# WiFly.net
KiCad netlist of a schematic drawn in EAGLE
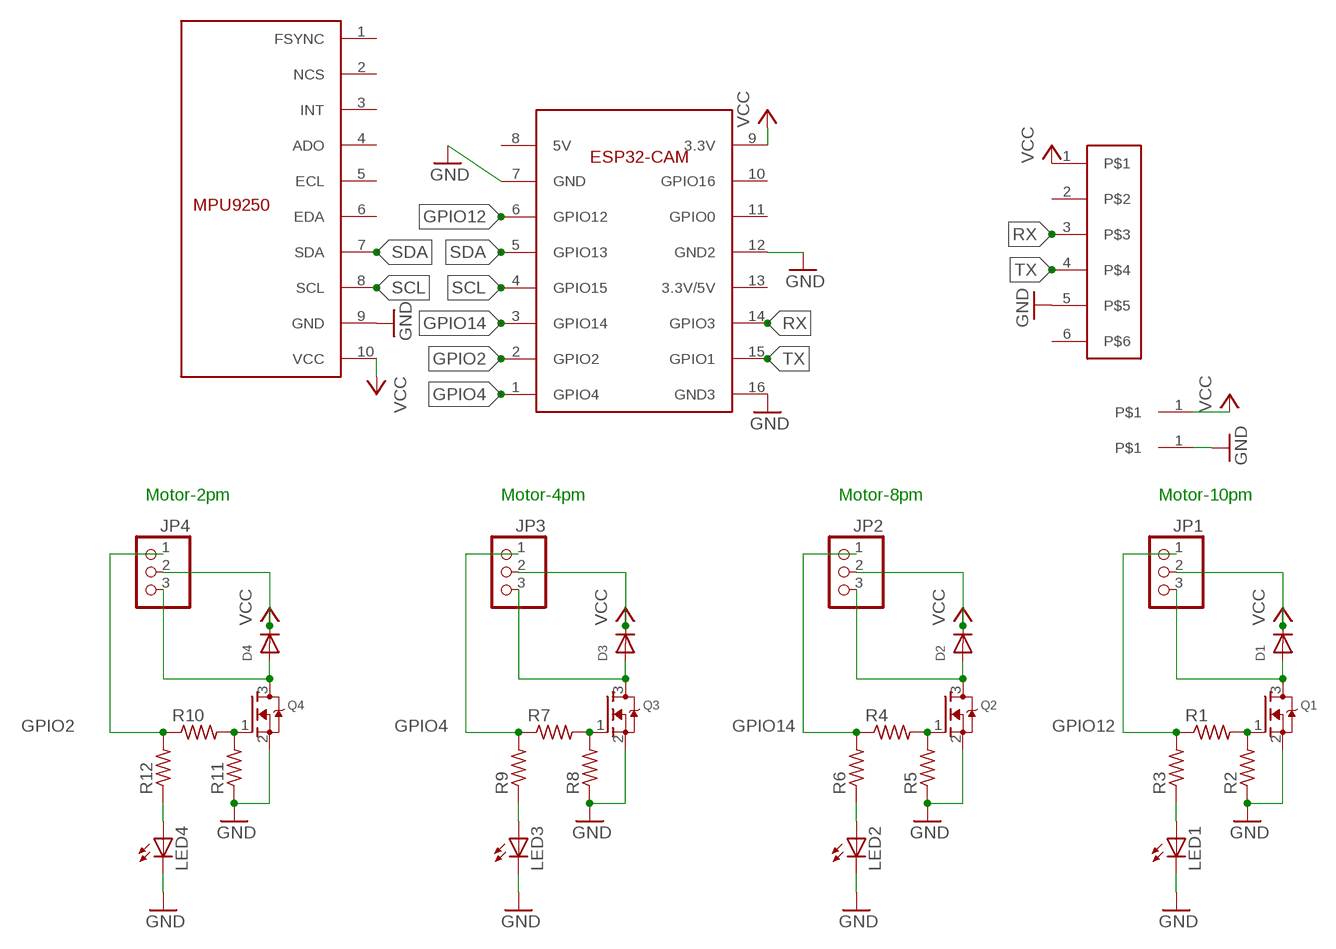
[diagram p0: schematic, sheet 1]

(export (version "E")
  (design (tool "Eeschema 10.0.6"))
  (components
    (comp (ref "+")
      (value "22AWG22AWG-MALE")
      (footprint "eagle-import:HDRV1W64P0_1X1_193X193X447B")
      (libsource (lib "eagle-import") (part "22AWG22AWG-MALE"))
    )
    (comp (ref "-")
      (value "22AWG22AWG-MALE")
      (footprint "eagle-import:HDRV1W64P0_1X1_193X193X447B")
      (libsource (lib "eagle-import") (part "22AWG22AWG-MALE"))
    )
    (comp (ref "D1")
      (value "DIODESOD-323F")
      (footprint "eagle-import:SOD-323F")
      (libsource (lib "eagle-import") (part "DIODESOD-323F"))
    )
    (comp (ref "D2")
      (value "DIODESOD-323F")
      (footprint "eagle-import:SOD-323F")
      (libsource (lib "eagle-import") (part "DIODESOD-323F"))
    )
    (comp (ref "D3")
      (value "DIODESOD-323F")
      (footprint "eagle-import:SOD-323F")
      (libsource (lib "eagle-import") (part "DIODESOD-323F"))
    )
    (comp (ref "D4")
      (value "DIODESOD-323F")
      (footprint "eagle-import:SOD-323F")
      (libsource (lib "eagle-import") (part "DIODESOD-323F"))
    )
    (comp (ref "JP1")
      (value "PINHD-1X3CB")
      (footprint "eagle-import:1X03-CLEANBIG")
      (libsource (lib "eagle-import") (part "PINHD-1X3CB"))
    )
    (comp (ref "JP2")
      (value "PINHD-1X3CB")
      (footprint "eagle-import:1X03-CLEANBIG")
      (libsource (lib "eagle-import") (part "PINHD-1X3CB"))
    )
    (comp (ref "JP3")
      (value "PINHD-1X3CB")
      (footprint "eagle-import:1X03-CLEANBIG")
      (libsource (lib "eagle-import") (part "PINHD-1X3CB"))
    )
    (comp (ref "JP4")
      (value "PINHD-1X3CB")
      (footprint "eagle-import:1X03-CLEANBIG")
      (libsource (lib "eagle-import") (part "PINHD-1X3CB"))
    )
    (comp (ref "LED1")
      (value "LEDCHIP-LED0603")
      (footprint "eagle-import:CHIP-LED0603")
      (libsource (lib "eagle-import") (part "LEDCHIP-LED0603"))
    )
    (comp (ref "LED2")
      (value "LEDCHIP-LED0603")
      (footprint "eagle-import:CHIP-LED0603")
      (libsource (lib "eagle-import") (part "LEDCHIP-LED0603"))
    )
    (comp (ref "LED3")
      (value "LEDCHIP-LED0603")
      (footprint "eagle-import:CHIP-LED0603")
      (libsource (lib "eagle-import") (part "LEDCHIP-LED0603"))
    )
    (comp (ref "LED4")
      (value "LEDCHIP-LED0603")
      (footprint "eagle-import:CHIP-LED0603")
      (libsource (lib "eagle-import") (part "LEDCHIP-LED0603"))
    )
    (comp (ref "Q1")
      (value "MOSFET-NREFLOW")
      (footprint "eagle-import:SOT23")
      (libsource (lib "eagle-import") (part "MOSFET-NREFLOW"))
    )
    (comp (ref "Q2")
      (value "MOSFET-NREFLOW")
      (footprint "eagle-import:SOT23")
      (libsource (lib "eagle-import") (part "MOSFET-NREFLOW"))
    )
    (comp (ref "Q3")
      (value "MOSFET-NREFLOW")
      (footprint "eagle-import:SOT23")
      (libsource (lib "eagle-import") (part "MOSFET-NREFLOW"))
    )
    (comp (ref "Q4")
      (value "MOSFET-NREFLOW")
      (footprint "eagle-import:SOT23")
      (libsource (lib "eagle-import") (part "MOSFET-NREFLOW"))
    )
    (comp (ref "R1")
      (value "R-US_R0603")
      (footprint "eagle-import:R0603")
      (libsource (lib "eagle-import") (part "R-US_R0603"))
    )
    (comp (ref "R2")
      (value "R-US_R0603")
      (footprint "eagle-import:R0603")
      (libsource (lib "eagle-import") (part "R-US_R0603"))
    )
    (comp (ref "R3")
      (value "R-US_R0603")
      (footprint "eagle-import:R0603")
      (libsource (lib "eagle-import") (part "R-US_R0603"))
    )
    (comp (ref "R4")
      (value "R-US_R0603")
      (footprint "eagle-import:R0603")
      (libsource (lib "eagle-import") (part "R-US_R0603"))
    )
    (comp (ref "R5")
      (value "R-US_R0603")
      (footprint "eagle-import:R0603")
      (libsource (lib "eagle-import") (part "R-US_R0603"))
    )
    (comp (ref "R6")
      (value "R-US_R0603")
      (footprint "eagle-import:R0603")
      (libsource (lib "eagle-import") (part "R-US_R0603"))
    )
    (comp (ref "R7")
      (value "R-US_R0603")
      (footprint "eagle-import:R0603")
      (libsource (lib "eagle-import") (part "R-US_R0603"))
    )
    (comp (ref "R8")
      (value "R-US_R0603")
      (footprint "eagle-import:R0603")
      (libsource (lib "eagle-import") (part "R-US_R0603"))
    )
    (comp (ref "R9")
      (value "R-US_R0603")
      (footprint "eagle-import:R0603")
      (libsource (lib "eagle-import") (part "R-US_R0603"))
    )
    (comp (ref "R10")
      (value "R-US_R0603")
      (footprint "eagle-import:R0603")
      (libsource (lib "eagle-import") (part "R-US_R0603"))
    )
    (comp (ref "R11")
      (value "R-US_R0603")
      (footprint "eagle-import:R0603")
      (libsource (lib "eagle-import") (part "R-US_R0603"))
    )
    (comp (ref "R12")
      (value "R-US_R0603")
      (footprint "eagle-import:R0603")
      (libsource (lib "eagle-import") (part "R-US_R0603"))
    )
    (comp (ref "U$1")
      (value "MPU9250FEMALE_HEADER")
      (footprint "eagle-import:HDRVR10W64P254_1X10_2540X254X254B")
      (libsource (lib "eagle-import") (part "MPU9250FEMALE_HEADER"))
    )
    (comp (ref "U$2")
      (value "ESP32-CAMESP32-CAM")
      (footprint "eagle-import:HDRVR16W64P2286X254_2X8_2032X2540X254B")
      (libsource (lib "eagle-import") (part "ESP32-CAMESP32-CAM"))
    )
    (comp (ref "U$3")
      (value "6-PINFEMALE-6-PIN-A")
      (footprint "eagle-import:HDRVR6W64P254_1X6_1524X254X762B")
      (libsource (lib "eagle-import") (part "6-PINFEMALE-6-PIN-A"))
    )
  )
  (nets
    (net (code "1") (name "GND") (class "Default")
      (node (ref "-") (pin "1") (pinfunction "P$1_1") (pintype "bidirectional"))
      (node (ref "LED1") (pin "C") (pinfunction "C_C") (pintype "passive"))
      (node (ref "LED2") (pin "C") (pinfunction "C_C") (pintype "passive"))
      (node (ref "LED3") (pin "C") (pinfunction "C_C") (pintype "passive"))
      (node (ref "LED4") (pin "C") (pinfunction "C_C") (pintype "passive"))
      (node (ref "Q1") (pin "2") (pinfunction "S_2") (pintype "bidirectional"))
      (node (ref "Q2") (pin "2") (pinfunction "S_2") (pintype "bidirectional"))
      (node (ref "Q3") (pin "2") (pinfunction "S_2") (pintype "bidirectional"))
      (node (ref "Q4") (pin "2") (pinfunction "S_2") (pintype "bidirectional"))
      (node (ref "R11") (pin "1") (pinfunction "1_1") (pintype "passive"))
      (node (ref "R2") (pin "1") (pinfunction "1_1") (pintype "passive"))
      (node (ref "R5") (pin "1") (pinfunction "1_1") (pintype "passive"))
      (node (ref "R8") (pin "1") (pinfunction "1_1") (pintype "passive"))
      (node (ref "U$1") (pin "9") (pinfunction "GND_9") (pintype "bidirectional"))
      (node (ref "U$2") (pin "12") (pinfunction "GND2_12") (pintype "bidirectional"))
      (node (ref "U$2") (pin "16") (pinfunction "GND3_16") (pintype "bidirectional"))
      (node (ref "U$2") (pin "7") (pinfunction "GND_7") (pintype "bidirectional"))
      (node (ref "U$3") (pin "5") (pinfunction "P$5_5") (pintype "bidirectional"))
    )
    (net (code "2") (name "GPIO2") (class "Default")
      (node (ref "JP4") (pin "1") (pinfunction "1_1") (pintype "passive"))
      (node (ref "R10") (pin "1") (pinfunction "1_1") (pintype "passive"))
      (node (ref "R12") (pin "2") (pinfunction "2_2") (pintype "passive"))
      (node (ref "U$2") (pin "2") (pinfunction "GPIO2_2") (pintype "bidirectional"))
    )
    (net (code "3") (name "GPIO4") (class "Default")
      (node (ref "JP3") (pin "1") (pinfunction "1_1") (pintype "passive"))
      (node (ref "R7") (pin "1") (pinfunction "1_1") (pintype "passive"))
      (node (ref "R9") (pin "2") (pinfunction "2_2") (pintype "passive"))
      (node (ref "U$2") (pin "1") (pinfunction "GPIO4_1") (pintype "bidirectional"))
    )
    (net (code "4") (name "GPIO12") (class "Default")
      (node (ref "JP1") (pin "1") (pinfunction "1_1") (pintype "passive"))
      (node (ref "R1") (pin "1") (pinfunction "1_1") (pintype "passive"))
      (node (ref "R3") (pin "2") (pinfunction "2_2") (pintype "passive"))
      (node (ref "U$2") (pin "6") (pinfunction "GPIO12_6") (pintype "bidirectional"))
    )
    (net (code "5") (name "GPIO14") (class "Default")
      (node (ref "JP2") (pin "1") (pinfunction "1_1") (pintype "passive"))
      (node (ref "R4") (pin "1") (pinfunction "1_1") (pintype "passive"))
      (node (ref "R6") (pin "2") (pinfunction "2_2") (pintype "passive"))
      (node (ref "U$2") (pin "3") (pinfunction "GPIO14_3") (pintype "bidirectional"))
    )
    (net (code "6") (name "Net-(LED1-PadA)") (class "Default")
      (node (ref "LED1") (pin "A") (pinfunction "A_A") (pintype "passive"))
      (node (ref "R3") (pin "1") (pinfunction "1_1") (pintype "passive"))
    )
    (net (code "7") (name "Net-(LED2-PadA)") (class "Default")
      (node (ref "LED2") (pin "A") (pinfunction "A_A") (pintype "passive"))
      (node (ref "R6") (pin "1") (pinfunction "1_1") (pintype "passive"))
    )
    (net (code "8") (name "Net-(LED3-PadA)") (class "Default")
      (node (ref "LED3") (pin "A") (pinfunction "A_A") (pintype "passive"))
      (node (ref "R9") (pin "1") (pinfunction "1_1") (pintype "passive"))
    )
    (net (code "9") (name "Net-(LED4-PadA)") (class "Default")
      (node (ref "LED4") (pin "A") (pinfunction "A_A") (pintype "passive"))
      (node (ref "R12") (pin "1") (pinfunction "1_1") (pintype "passive"))
    )
    (net (code "10") (name "Net-(Q1-D)") (class "Default")
      (node (ref "D1") (pin "A") (pinfunction "A_A") (pintype "passive"))
      (node (ref "JP1") (pin "3") (pinfunction "3_3") (pintype "passive"))
      (node (ref "Q1") (pin "3") (pinfunction "D_3") (pintype "bidirectional"))
    )
    (net (code "11") (name "Net-(Q1-G)") (class "Default")
      (node (ref "Q1") (pin "1") (pinfunction "G_1") (pintype "bidirectional"))
      (node (ref "R1") (pin "2") (pinfunction "2_2") (pintype "passive"))
      (node (ref "R2") (pin "2") (pinfunction "2_2") (pintype "passive"))
    )
    (net (code "12") (name "Net-(Q2-D)") (class "Default")
      (node (ref "D2") (pin "A") (pinfunction "A_A") (pintype "passive"))
      (node (ref "JP2") (pin "3") (pinfunction "3_3") (pintype "passive"))
      (node (ref "Q2") (pin "3") (pinfunction "D_3") (pintype "bidirectional"))
    )
    (net (code "13") (name "Net-(Q2-G)") (class "Default")
      (node (ref "Q2") (pin "1") (pinfunction "G_1") (pintype "bidirectional"))
      (node (ref "R4") (pin "2") (pinfunction "2_2") (pintype "passive"))
      (node (ref "R5") (pin "2") (pinfunction "2_2") (pintype "passive"))
    )
    (net (code "14") (name "Net-(Q3-D)") (class "Default")
      (node (ref "D3") (pin "A") (pinfunction "A_A") (pintype "passive"))
      (node (ref "JP3") (pin "3") (pinfunction "3_3") (pintype "passive"))
      (node (ref "Q3") (pin "3") (pinfunction "D_3") (pintype "bidirectional"))
    )
    (net (code "15") (name "Net-(Q3-G)") (class "Default")
      (node (ref "Q3") (pin "1") (pinfunction "G_1") (pintype "bidirectional"))
      (node (ref "R7") (pin "2") (pinfunction "2_2") (pintype "passive"))
      (node (ref "R8") (pin "2") (pinfunction "2_2") (pintype "passive"))
    )
    (net (code "16") (name "Net-(Q4-D)") (class "Default")
      (node (ref "D4") (pin "A") (pinfunction "A_A") (pintype "passive"))
      (node (ref "JP4") (pin "3") (pinfunction "3_3") (pintype "passive"))
      (node (ref "Q4") (pin "3") (pinfunction "D_3") (pintype "bidirectional"))
    )
    (net (code "17") (name "Net-(Q4-G)") (class "Default")
      (node (ref "Q4") (pin "1") (pinfunction "G_1") (pintype "bidirectional"))
      (node (ref "R10") (pin "2") (pinfunction "2_2") (pintype "passive"))
      (node (ref "R11") (pin "2") (pinfunction "2_2") (pintype "passive"))
    )
    (net (code "18") (name "RX") (class "Default")
      (node (ref "U$2") (pin "14") (pinfunction "GPIO3_14") (pintype "bidirectional"))
      (node (ref "U$3") (pin "3") (pinfunction "P$3_3") (pintype "bidirectional"))
    )
    (net (code "19") (name "SCL") (class "Default")
      (node (ref "U$1") (pin "8") (pinfunction "SCL_8") (pintype "bidirectional"))
      (node (ref "U$2") (pin "4") (pinfunction "GPIO15_4") (pintype "bidirectional"))
    )
    (net (code "20") (name "SDA") (class "Default")
      (node (ref "U$1") (pin "7") (pinfunction "SDA_7") (pintype "bidirectional"))
      (node (ref "U$2") (pin "5") (pinfunction "GPIO13_5") (pintype "bidirectional"))
    )
    (net (code "21") (name "TX") (class "Default")
      (node (ref "U$2") (pin "15") (pinfunction "GPIO1_15") (pintype "bidirectional"))
      (node (ref "U$3") (pin "4") (pinfunction "P$4_4") (pintype "bidirectional"))
    )
    (net (code "22") (name "VCC") (class "Default")
      (node (ref "+") (pin "1") (pinfunction "P$1_1") (pintype "bidirectional"))
      (node (ref "D1") (pin "C") (pinfunction "C_C") (pintype "passive"))
      (node (ref "D2") (pin "C") (pinfunction "C_C") (pintype "passive"))
      (node (ref "D3") (pin "C") (pinfunction "C_C") (pintype "passive"))
      (node (ref "D4") (pin "C") (pinfunction "C_C") (pintype "passive"))
      (node (ref "JP1") (pin "2") (pinfunction "2_2") (pintype "passive"))
      (node (ref "JP2") (pin "2") (pinfunction "2_2") (pintype "passive"))
      (node (ref "JP3") (pin "2") (pinfunction "2_2") (pintype "passive"))
      (node (ref "JP4") (pin "2") (pinfunction "2_2") (pintype "passive"))
      (node (ref "U$1") (pin "10") (pinfunction "VCC_10") (pintype "bidirectional"))
      (node (ref "U$2") (pin "9") (pinfunction "3.3V_9") (pintype "bidirectional"))
      (node (ref "U$3") (pin "1") (pinfunction "P$1_1") (pintype "bidirectional"))
    )
    (net (code "23") (name "unconnected-(U$1-ADO-Pad4)") (class "Default")
      (node (ref "U$1") (pin "4") (pinfunction "ADO_4") (pintype "bidirectional"))
    )
    (net (code "24") (name "unconnected-(U$1-ECL-Pad5)") (class "Default")
      (node (ref "U$1") (pin "5") (pinfunction "ECL_5") (pintype "bidirectional"))
    )
    (net (code "25") (name "unconnected-(U$1-EDA-Pad6)") (class "Default")
      (node (ref "U$1") (pin "6") (pinfunction "EDA_6") (pintype "bidirectional"))
    )
    (net (code "26") (name "unconnected-(U$1-FSYNC-Pad1)") (class "Default")
      (node (ref "U$1") (pin "1") (pinfunction "FSYNC_1") (pintype "bidirectional"))
    )
    (net (code "27") (name "unconnected-(U$1-INT-Pad3)") (class "Default")
      (node (ref "U$1") (pin "3") (pinfunction "INT_3") (pintype "bidirectional"))
    )
    (net (code "28") (name "unconnected-(U$1-NCS-Pad2)") (class "Default")
      (node (ref "U$1") (pin "2") (pinfunction "NCS_2") (pintype "bidirectional"))
    )
    (net (code "29") (name "unconnected-(U$2-3.3V{slash}5V-Pad13)") (class "Default")
      (node (ref "U$2") (pin "13") (pinfunction "3.3V/5V_13") (pintype "bidirectional"))
    )
    (net (code "30") (name "unconnected-(U$2-5V-Pad8)") (class "Default")
      (node (ref "U$2") (pin "8") (pinfunction "5V_8") (pintype "bidirectional"))
    )
    (net (code "31") (name "unconnected-(U$2-GPIO0-Pad11)") (class "Default")
      (node (ref "U$2") (pin "11") (pinfunction "GPIO0_11") (pintype "bidirectional"))
    )
    (net (code "32") (name "unconnected-(U$2-GPIO16-Pad10)") (class "Default")
      (node (ref "U$2") (pin "10") (pinfunction "GPIO16_10") (pintype "bidirectional"))
    )
    (net (code "33") (name "unconnected-(U$3-P$2-Pad2)") (class "Default")
      (node (ref "U$3") (pin "2") (pinfunction "P$2_2") (pintype "bidirectional"))
    )
    (net (code "34") (name "unconnected-(U$3-P$6-Pad6)") (class "Default")
      (node (ref "U$3") (pin "6") (pinfunction "P$6_6") (pintype "bidirectional"))
    )
  )
)
